# sd_card.net
KiCad netlist of a schematic drawn in Altium Designer
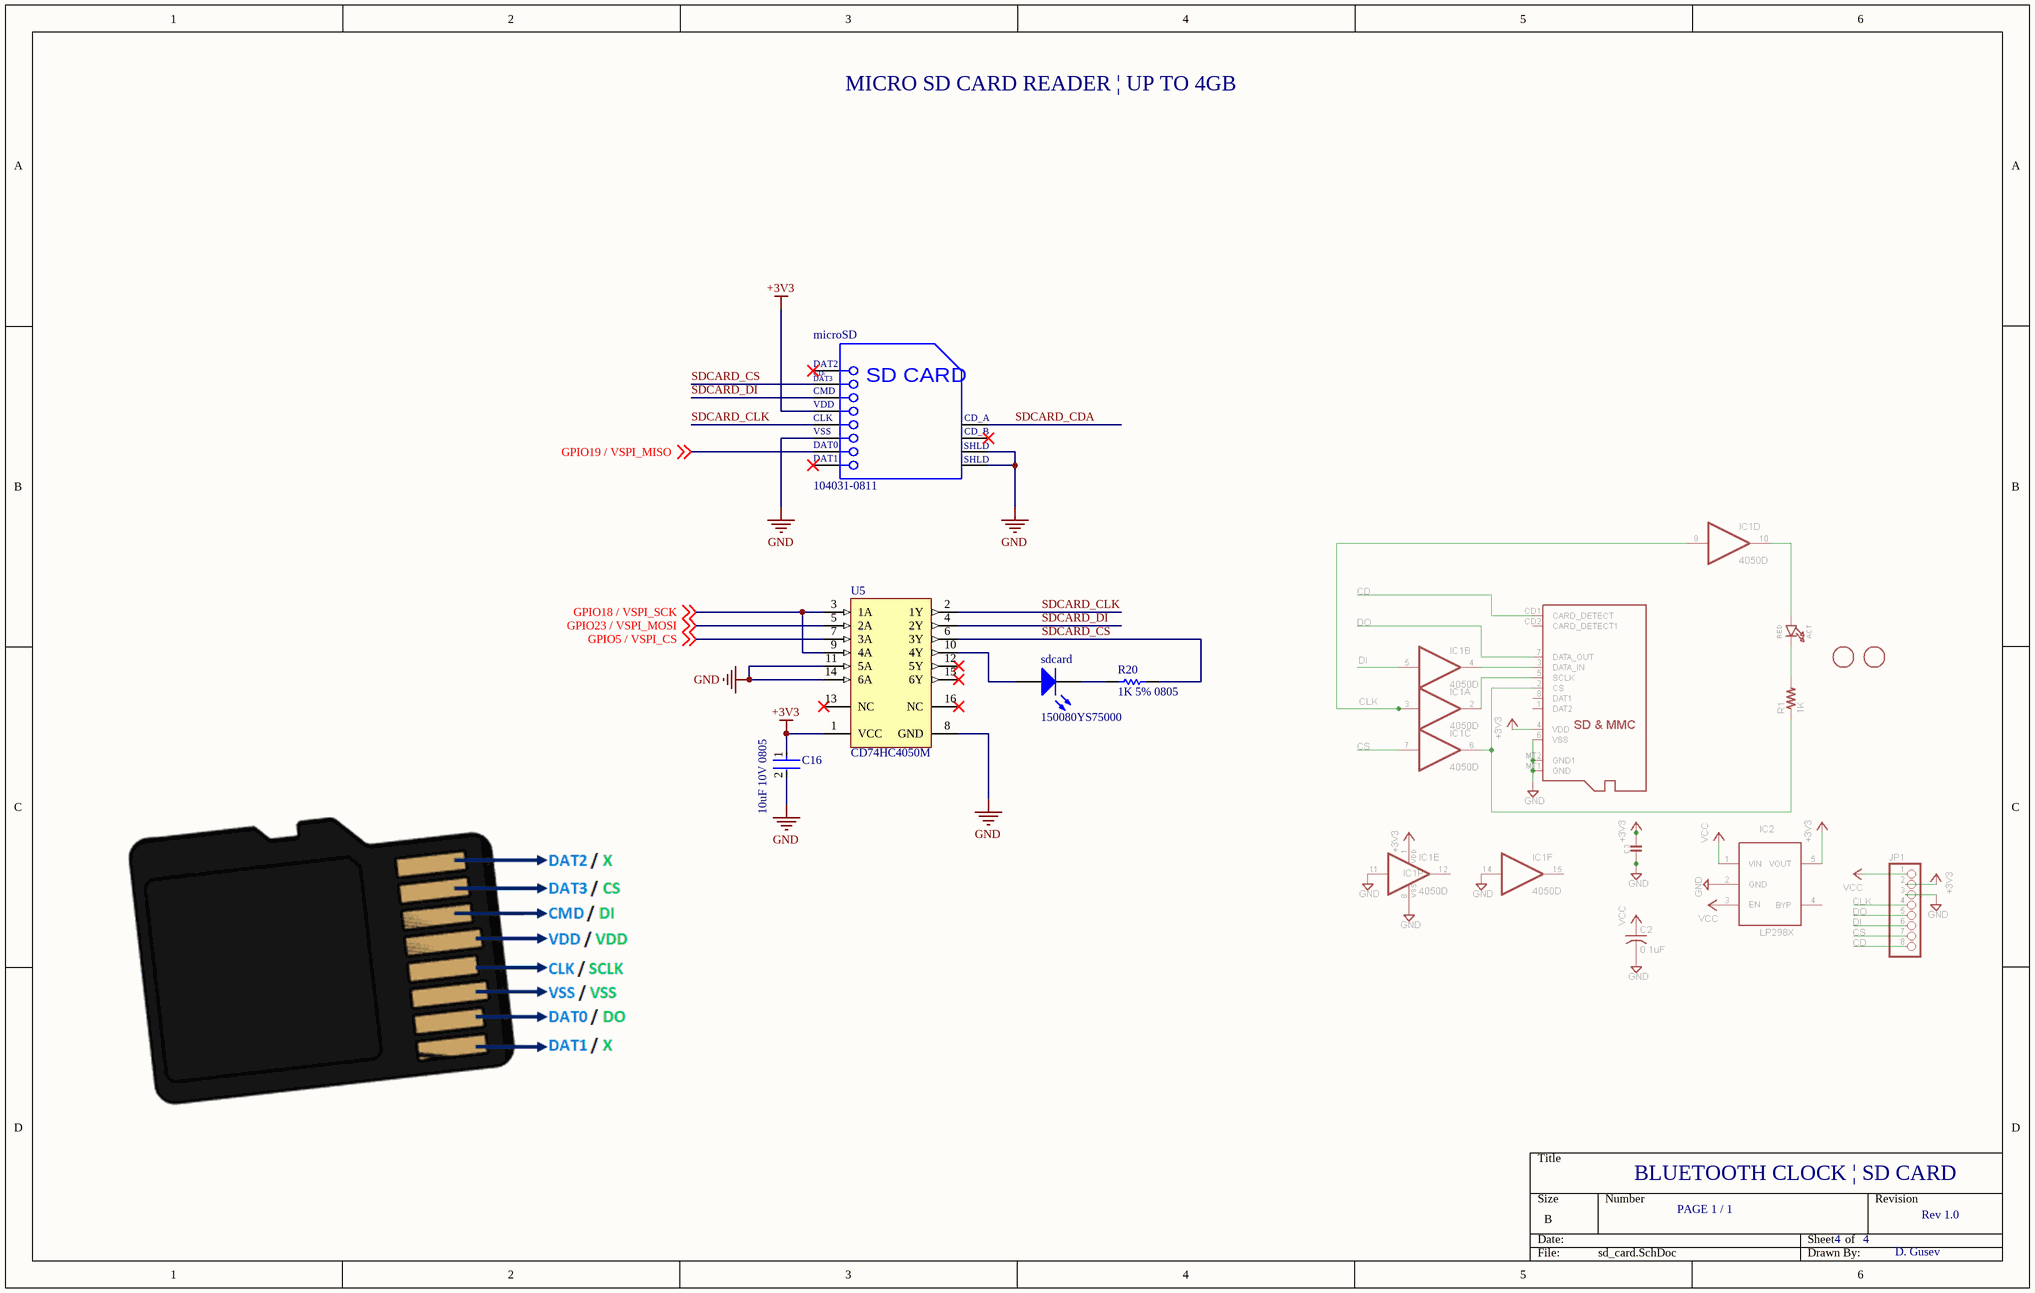
[diagram p0: sd_card.SchDoc]

(export (version "E")
  (design (tool "Eeschema 10.0.6"))
  (components
    (comp (ref "C16")
      (value "10uF 10V 0805")
      (footprint "FP-C0805C-DG-MFG")
      (description "CAP CER 10UF 10V X5R 0805")
      (fields (field (name "TOLERANCE") "10%") (field (name "MANUFACTURER PART NUMBER") "C0805C106K8PACTU"))
      (libsource (lib "Altium Content Vault") (part "11868f565c42a9108669ba33697ecf6"))
    )
    (comp (ref "microSD")
      (value "104031-0811")
      (footprint "MOLX-104031-0811_V")
      (description "Micro SD Card, RA, -25 to 85 degC, 8-Pin SMD, RoHS, Tape and Reel")
      (fields (field (name "MANUFACTURER") "Molex"))
      (libsource (lib "Altium Content Vault") (part "CN-SD-8-2SW-2S"))
    )
    (comp (ref "R20")
      (value "1K 5% 0805")
      (footprint "RESC2013X60X40ML20T25")
      (fields (field (name "PART NUMBER") "ERA6AEB123V") (field (name "MANUFACTURER") "Panasonic"))
      (libsource (lib "Altium Content Vault") (part "RES"))
    )
    (comp (ref "sdcard")
      (value "150080YS75000")
      (footprint "0805_A")
      (description "SMD mono-color Chip LED, WL-SMCW, Yellow")
      (fields (field (name "MANUFACTURER") "Wuerth Elektronik"))
      (libsource (lib "Altium Content Vault") (part "WE-LED_K1A2-2"))
    )
    (comp (ref "U5")
      (value "CD74HC4050M")
      (footprint "D0016A_M")
      (description "High Speed CMOS Logic Hex Non-Inverting Buffers, D0016A, TUBE")
      (fields
        (field (name "MANUFACTURER") "Texas Instruments")
        (field (name "GENERIC PART NUMBER") "CD74HC4050")
      )
      (libsource (lib "Altium Content Vault") (part "TI-CDX4HC4050-16"))
    )
  )
  (nets
    (net (code "1") (name "+3V3") (class "Default")
      (node (ref "C16") (pin "1") (pinfunction "1_1") (pintype "passive"))
      (node (ref "U5") (pin "1") (pinfunction "VCC_1") (pintype "power_in"))
      (node (ref "microSD") (pin "4") (pinfunction "VDD_4") (pintype "passive"))
    )
    (net (code "2") (name "/SDCARD_CDA") (class "Default")
      (node (ref "microSD") (pin "9") (pinfunction "CD_A_9") (pintype "passive"))
    )
    (net (code "3") (name "/SDCARD_CLK") (class "Default")
      (node (ref "U5") (pin "2") (pinfunction "1Y_2") (pintype "output"))
      (node (ref "microSD") (pin "5") (pinfunction "CLK_5") (pintype "passive"))
    )
    (net (code "4") (name "/SDCARD_CS") (class "Default")
      (node (ref "R20") (pin "2") (pinfunction "2_2") (pintype "passive"))
      (node (ref "U5") (pin "6") (pinfunction "3Y_6") (pintype "output"))
      (node (ref "microSD") (pin "2") (pinfunction "CMD_2") (pintype "passive"))
    )
    (net (code "5") (name "/SDCARD_DI") (class "Default")
      (node (ref "U5") (pin "4") (pinfunction "2Y_4") (pintype "output"))
      (node (ref "microSD") (pin "3") (pinfunction "VSS1_3") (pintype "passive"))
    )
    (net (code "6") (name "GND") (class "Default")
      (node (ref "C16") (pin "2") (pinfunction "2_2") (pintype "passive"))
      (node (ref "U5") (pin "11") (pinfunction "5A_11") (pintype "input"))
      (node (ref "U5") (pin "14") (pinfunction "6A_14") (pintype "input"))
      (node (ref "U5") (pin "8") (pinfunction "GND_8") (pintype "power_in"))
      (node (ref "microSD") (pin "11") (pinfunction "SHLD1_11") (pintype "passive"))
      (node (ref "microSD") (pin "12") (pinfunction "SHLD2_12") (pintype "passive"))
      (node (ref "microSD") (pin "6") (pinfunction "VSS2_6") (pintype "passive"))
    )
    (net (code "7") (name "GPIO5 {slash} VSPI_CS") (class "Default")
      (node (ref "U5") (pin "7") (pinfunction "3A_7") (pintype "input"))
    )
    (net (code "8") (name "GPIO18 {slash} VSPI_SCK") (class "Default")
      (node (ref "U5") (pin "3") (pinfunction "1A_3") (pintype "input"))
      (node (ref "U5") (pin "9") (pinfunction "4A_9") (pintype "input"))
    )
    (net (code "9") (name "GPIO19 {slash} VSPI_MISO") (class "Default")
      (node (ref "microSD") (pin "7") (pinfunction "DAT0_7") (pintype "passive"))
    )
    (net (code "10") (name "GPIO23 {slash} VSPI_MOSI") (class "Default")
      (node (ref "U5") (pin "5") (pinfunction "2A_5") (pintype "input"))
    )
    (net (code "11") (name "Net-(U5-4Y)") (class "Default")
      (node (ref "U5") (pin "10") (pinfunction "4Y_10") (pintype "output"))
      (node (ref "sdcard") (pin "2") (pinfunction "A_2") (pintype "passive"))
    )
    (net (code "12") (name "Net-(sdcard-K)") (class "Default")
      (node (ref "R20") (pin "1") (pinfunction "1_1") (pintype "passive"))
      (node (ref "sdcard") (pin "1") (pinfunction "K_1") (pintype "passive"))
    )
    (net (code "13") (name "unconnected-(U5-5Y-Pad12)") (class "Default")
      (node (ref "U5") (pin "12") (pinfunction "5Y_12") (pintype "output+no_connect"))
    )
    (net (code "14") (name "unconnected-(U5-6Y-Pad15)") (class "Default")
      (node (ref "U5") (pin "15") (pinfunction "6Y_15") (pintype "output+no_connect"))
    )
    (net (code "15") (name "unconnected-(U5-NC-Pad13)") (class "Default")
      (node (ref "U5") (pin "13") (pinfunction "NC_13") (pintype "passive+no_connect"))
    )
    (net (code "16") (name "unconnected-(U5-NC-Pad16)") (class "Default")
      (node (ref "U5") (pin "16") (pinfunction "NC_16") (pintype "passive+no_connect"))
    )
    (net (code "17") (name "unconnected-(microSD-CD_B-Pad10)") (class "Default")
      (node (ref "microSD") (pin "10") (pinfunction "CD_B_10") (pintype "passive+no_connect"))
    )
    (net (code "18") (name "unconnected-(microSD-CD{slash}DAT3-Pad1)") (class "Default")
      (node (ref "microSD") (pin "1") (pinfunction "CD/DAT3_1") (pintype "passive+no_connect"))
    )
    (net (code "19") (name "unconnected-(microSD-DAT1-Pad8)") (class "Default")
      (node (ref "microSD") (pin "8") (pinfunction "DAT1_8") (pintype "passive+no_connect"))
    )
  )
)
